# BreakOut_20172.net
KiCad netlist of a schematic drawn in Altium Designer
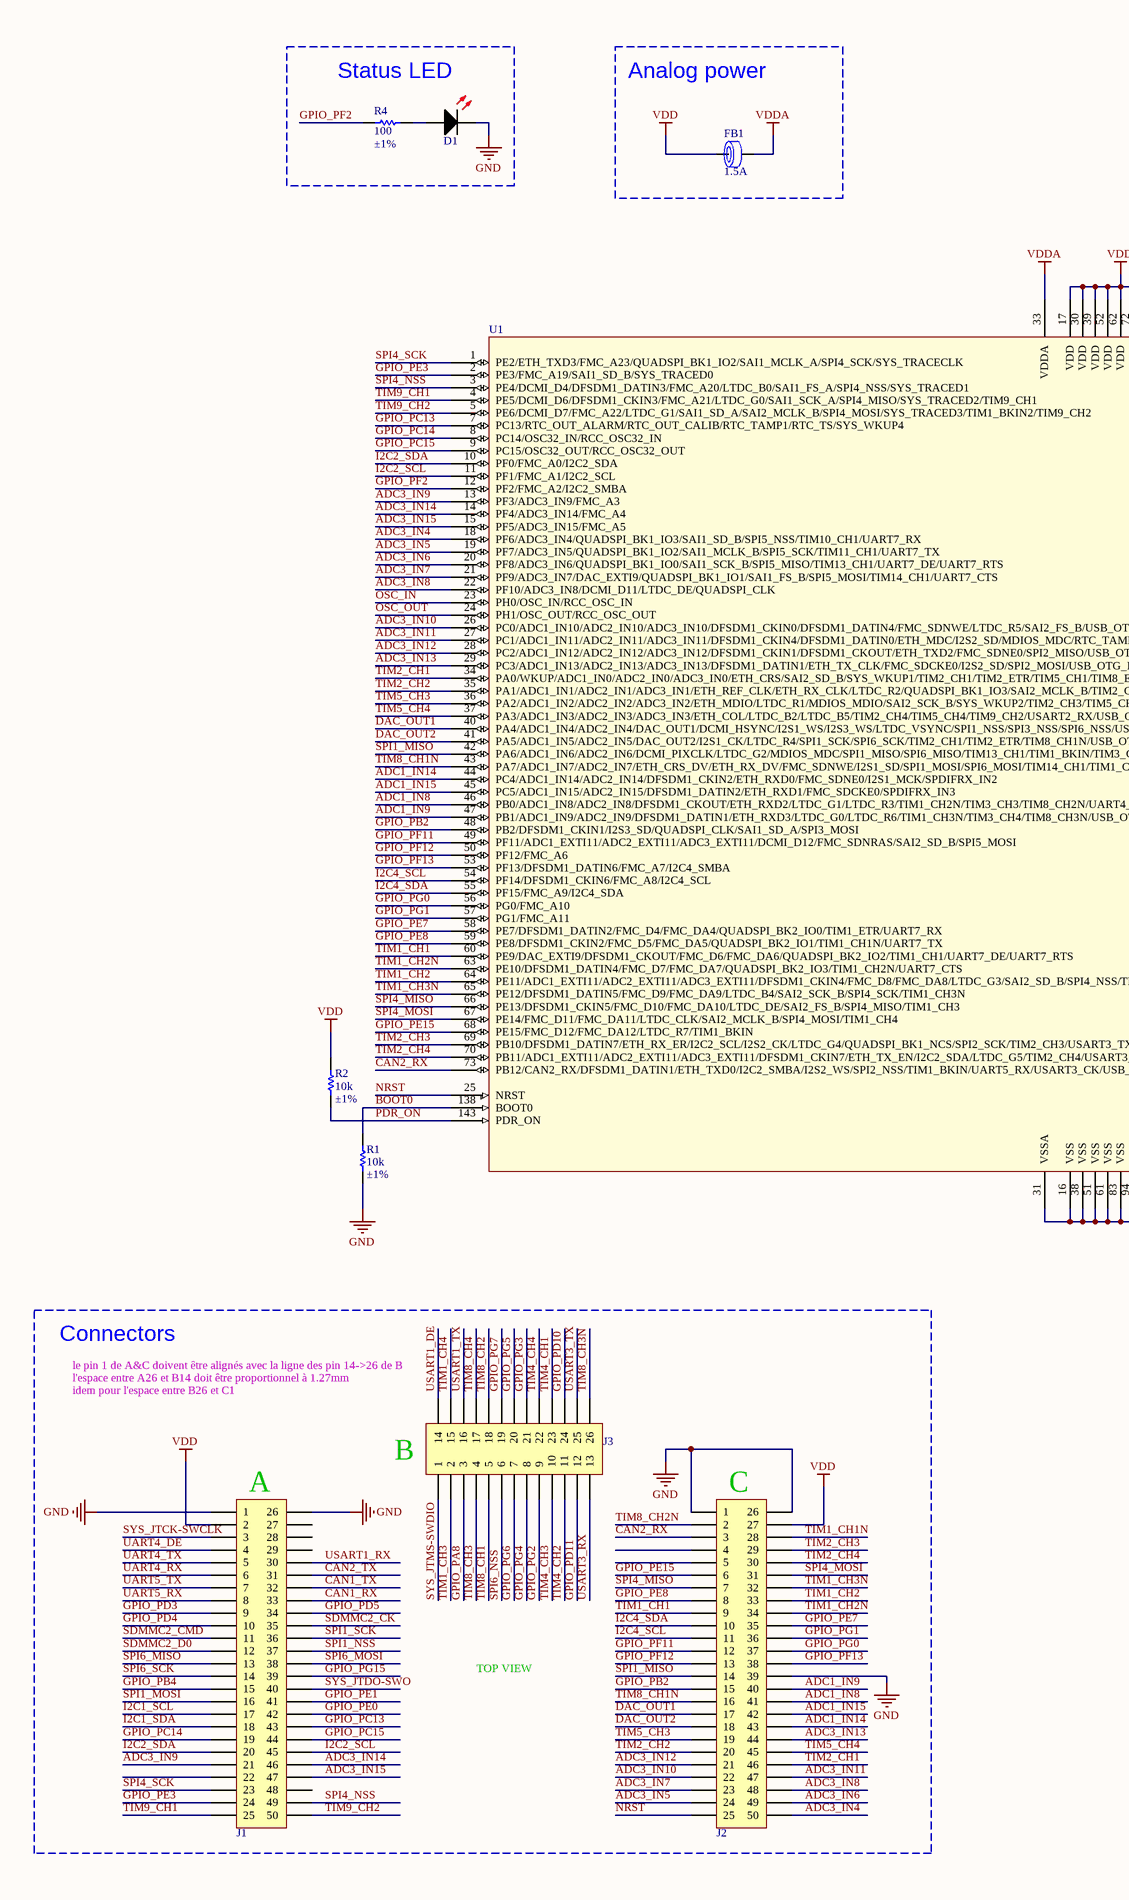
[diagram p0: BreakOut_20172.SchDoc, left]
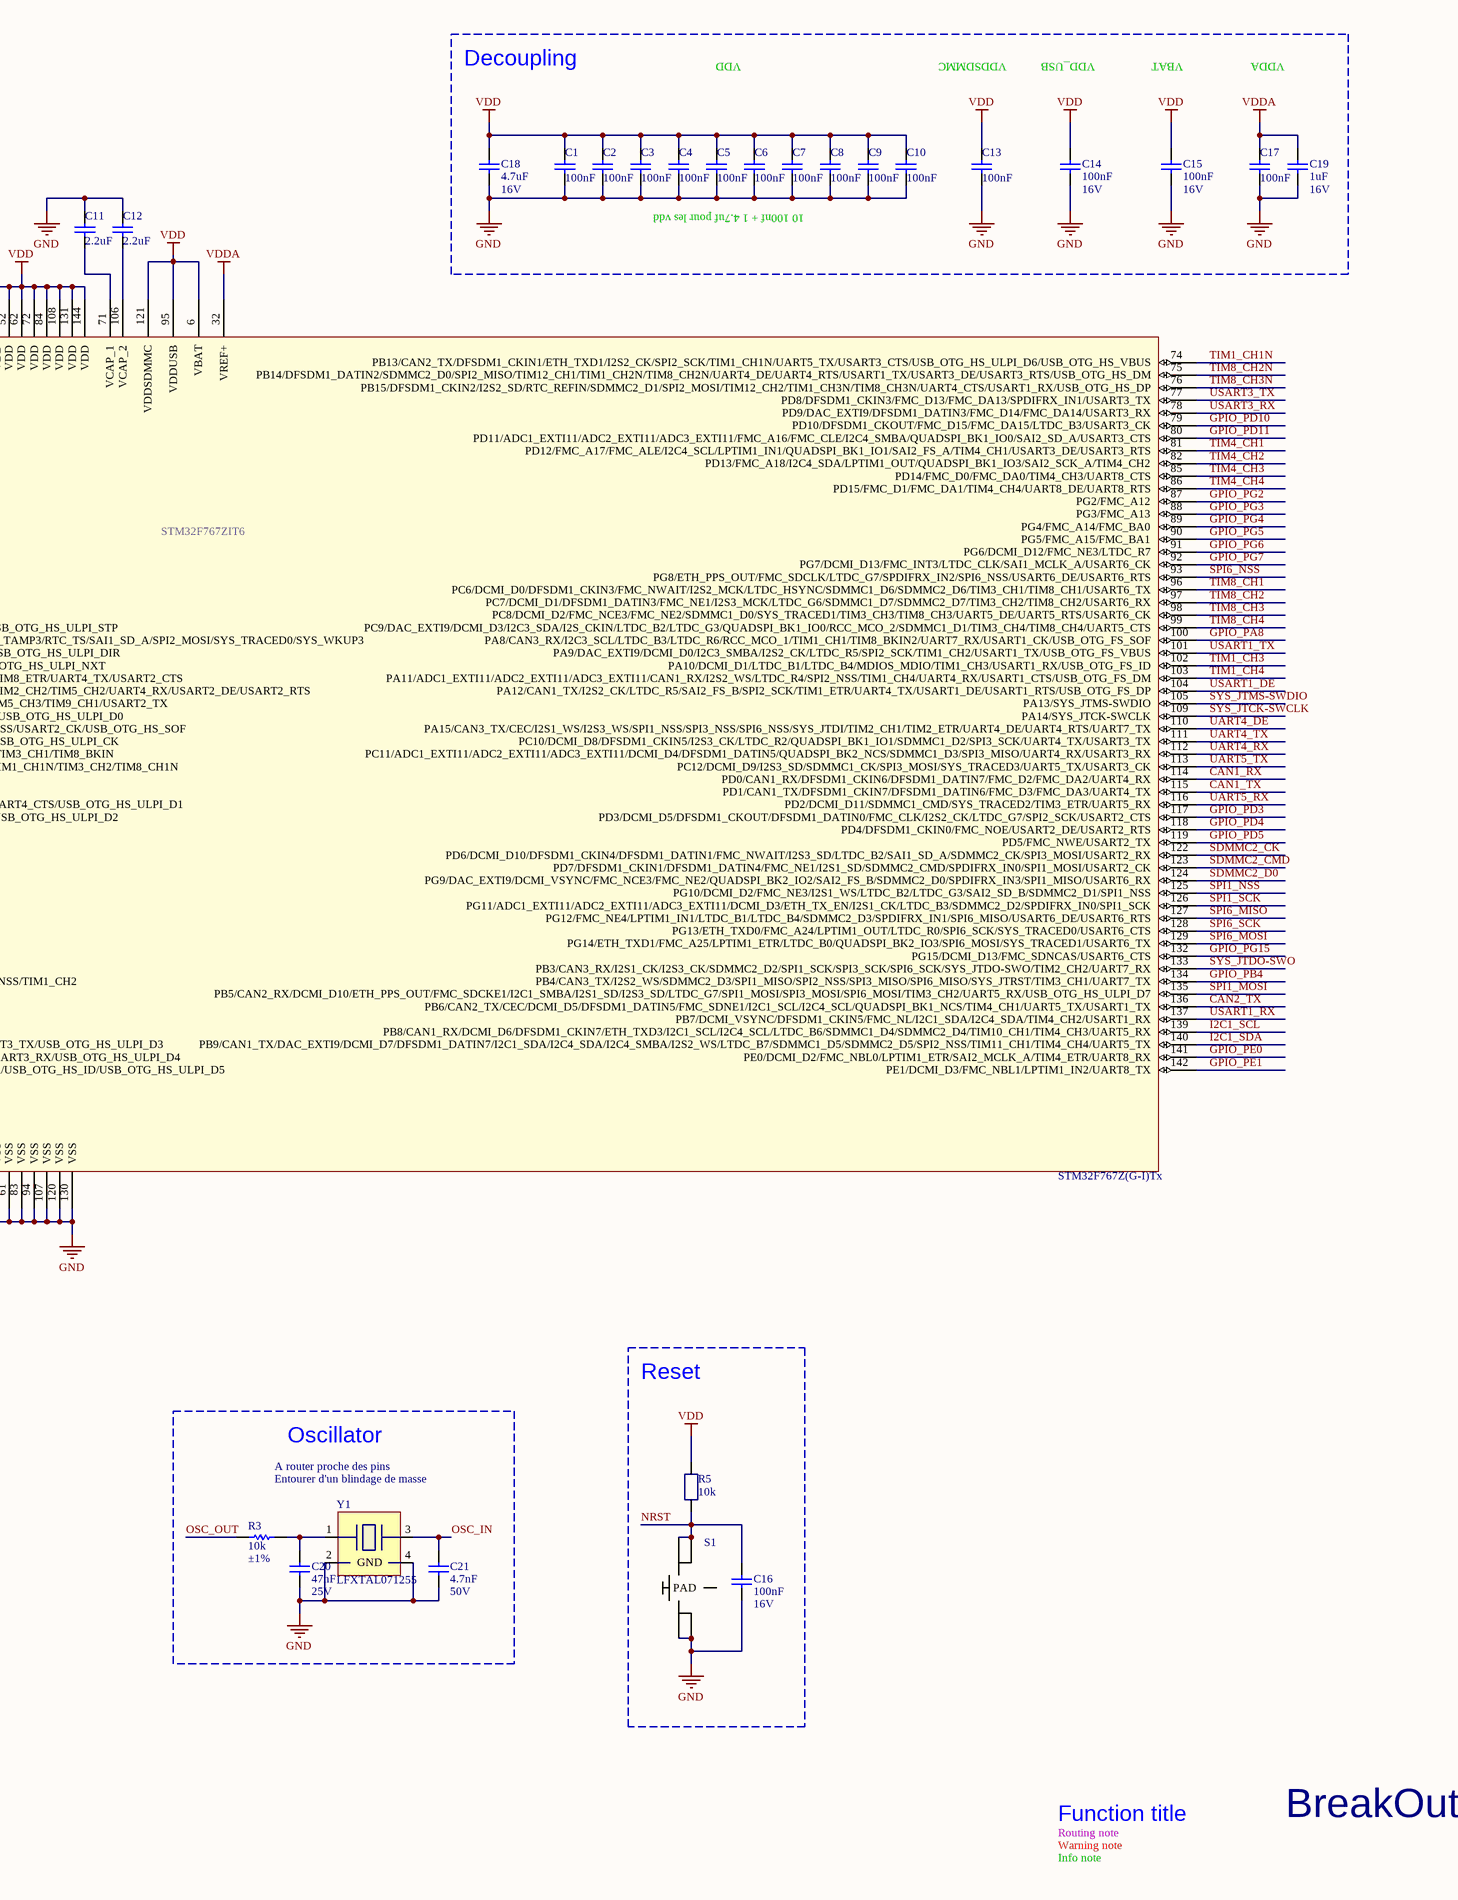
[diagram p1: BreakOut_20172.SchDoc, right]

(export (version "E")
  (design (tool "Eeschema 10.0.6"))
  (components
    (comp (ref "C1")
      (value "100nF")
      (footprint "WCAP-CSGP_0402, 1x0.5x0.5")
      (description "CAP CER 100nF 16V X7R 0402")
      (fields
        (field (name "MANUFACTURER") "Wurth Elektronik")
        (field (name "MANUFACTURER PART NUMBER") "885012205037")
      )
      (libsource (lib "Condensateur") (part "WCAP-CSGP, 885012205037"))
    )
    (comp (ref "C2")
      (value "100nF")
      (footprint "WCAP-CSGP_0402, 1x0.5x0.5")
      (description "CAP CER 100nF 16V X7R 0402")
      (fields
        (field (name "MANUFACTURER") "Wurth Elektronik")
        (field (name "MANUFACTURER PART NUMBER") "885012205037")
      )
      (libsource (lib "Condensateur") (part "WCAP-CSGP, 885012205037"))
    )
    (comp (ref "C3")
      (value "100nF")
      (footprint "WCAP-CSGP_0402, 1x0.5x0.5")
      (description "CAP CER 100nF 16V X7R 0402")
      (fields
        (field (name "MANUFACTURER") "Wurth Elektronik")
        (field (name "MANUFACTURER PART NUMBER") "885012205037")
      )
      (libsource (lib "Condensateur") (part "WCAP-CSGP, 885012205037"))
    )
    (comp (ref "C4")
      (value "100nF")
      (footprint "WCAP-CSGP_0402, 1x0.5x0.5")
      (description "CAP CER 100nF 16V X7R 0402")
      (fields
        (field (name "MANUFACTURER") "Wurth Elektronik")
        (field (name "MANUFACTURER PART NUMBER") "885012205037")
      )
      (libsource (lib "Condensateur") (part "WCAP-CSGP, 885012205037"))
    )
    (comp (ref "C5")
      (value "100nF")
      (footprint "WCAP-CSGP_0402, 1x0.5x0.5")
      (description "CAP CER 100nF 16V X7R 0402")
      (fields
        (field (name "MANUFACTURER") "Wurth Elektronik")
        (field (name "MANUFACTURER PART NUMBER") "885012205037")
      )
      (libsource (lib "Condensateur") (part "WCAP-CSGP, 885012205037"))
    )
    (comp (ref "C6")
      (value "100nF")
      (footprint "WCAP-CSGP_0402, 1x0.5x0.5")
      (description "CAP CER 100nF 16V X7R 0402")
      (fields
        (field (name "MANUFACTURER") "Wurth Elektronik")
        (field (name "MANUFACTURER PART NUMBER") "885012205037")
      )
      (libsource (lib "Condensateur") (part "WCAP-CSGP, 885012205037"))
    )
    (comp (ref "C7")
      (value "100nF")
      (footprint "WCAP-CSGP_0402, 1x0.5x0.5")
      (description "CAP CER 100nF 16V X7R 0402")
      (fields
        (field (name "MANUFACTURER") "Wurth Elektronik")
        (field (name "MANUFACTURER PART NUMBER") "885012205037")
      )
      (libsource (lib "Condensateur") (part "WCAP-CSGP, 885012205037"))
    )
    (comp (ref "C8")
      (value "100nF")
      (footprint "WCAP-CSGP_0402, 1x0.5x0.5")
      (description "CAP CER 100nF 16V X7R 0402")
      (fields
        (field (name "MANUFACTURER") "Wurth Elektronik")
        (field (name "MANUFACTURER PART NUMBER") "885012205037")
      )
      (libsource (lib "Condensateur") (part "WCAP-CSGP, 885012205037"))
    )
    (comp (ref "C9")
      (value "100nF")
      (footprint "WCAP-CSGP_0402, 1x0.5x0.5")
      (description "CAP CER 100nF 16V X7R 0402")
      (fields
        (field (name "MANUFACTURER") "Wurth Elektronik")
        (field (name "MANUFACTURER PART NUMBER") "885012205037")
      )
      (libsource (lib "Condensateur") (part "WCAP-CSGP, 885012205037"))
    )
    (comp (ref "C10")
      (value "100nF")
      (footprint "WCAP-CSGP_0402, 1x0.5x0.5")
      (description "CAP CER 100nF 16V X7R 0402")
      (fields
        (field (name "MANUFACTURER") "Wurth Elektronik")
        (field (name "MANUFACTURER PART NUMBER") "885012205037")
      )
      (libsource (lib "Condensateur") (part "WCAP-CSGP, 885012205037"))
    )
    (comp (ref "C11")
      (value "2.2uF")
      (footprint "WCAP-CSGP_0603, 1.6x0.8x0.8")
      (description "CAP CER 2.2uF 10V X7R 0603")
      (fields
        (field (name "MANUFACTURER") "Wurth Elektronik")
        (field (name "MANUFACTURER PART NUMBER") "885012206027")
      )
      (libsource (lib "Condensateur") (part "WCAP-CSGP, 885012206027"))
    )
    (comp (ref "C12")
      (value "2.2uF")
      (footprint "WCAP-CSGP_0603, 1.6x0.8x0.8")
      (description "CAP CER 2.2uF 10V X7R 0603")
      (fields
        (field (name "MANUFACTURER") "Wurth Elektronik")
        (field (name "MANUFACTURER PART NUMBER") "885012206027")
      )
      (libsource (lib "Condensateur") (part "WCAP-CSGP, 885012206027"))
    )
    (comp (ref "C13")
      (value "100nF")
      (footprint "WCAP-CSGP_0402, 1x0.5x0.5")
      (description "CAP CER 100nF 16V X7R 0402")
      (fields
        (field (name "MANUFACTURER") "Wurth Elektronik")
        (field (name "MANUFACTURER PART NUMBER") "885012205037")
      )
      (libsource (lib "Condensateur") (part "WCAP-CSGP, 885012205037"))
    )
    (comp (ref "C14")
      (value "100nF")
      (footprint "WCAP-CSGP_0402, 1x0.5x0.5")
      (description "CAP CER 100nF 16V X7R 0402")
      (fields
        (field (name "MANUFACTURER") "Wurth Elektronik")
        (field (name "MANUFACTURER PART NUMBER") "885012205037")
        (field (name "RATEDVOLTAGE") "16V")
      )
      (libsource (lib "Condensateur") (part "WCAP-CSGP, 885012205037"))
    )
    (comp (ref "C15")
      (value "100nF")
      (footprint "WCAP-CSGP_0402, 1x0.5x0.5")
      (description "CAP CER 100nF 16V X7R 0402")
      (fields
        (field (name "MANUFACTURER") "Wurth Elektronik")
        (field (name "MANUFACTURER PART NUMBER") "885012205037")
        (field (name "RATEDVOLTAGE") "16V")
      )
      (libsource (lib "Condensateur") (part "WCAP-CSGP, 885012205037"))
    )
    (comp (ref "C16")
      (value "100nF")
      (footprint "WCAP-CSGP_0402, 1x0.5x0.5")
      (description "CAP CER 100nF 16V X7R 0402")
      (fields
        (field (name "MANUFACTURER") "Wurth Elektronik")
        (field (name "MANUFACTURER PART NUMBER") "885012205037")
        (field (name "RATEDVOLTAGE") "16V")
      )
      (libsource (lib "Condensateur") (part "WCAP-CSGP, 885012205037"))
    )
    (comp (ref "C17")
      (value "100nF")
      (footprint "WCAP-CSGP_0402, 1x0.5x0.5")
      (description "CAP CER 100nF 16V X7R 0402")
      (fields
        (field (name "MANUFACTURER") "Wurth Elektronik")
        (field (name "MANUFACTURER PART NUMBER") "885012205037")
      )
      (libsource (lib "Condensateur") (part "WCAP-CSGP, 885012205037"))
    )
    (comp (ref "C18")
      (value "4.7uF")
      (footprint "WCAP-CSGP_0805, 2x1.25x1.25")
      (description "CAP CER 4.7uF 16V X7R 0805")
      (fields
        (field (name "MANUFACTURER") "Wurth Elektronik")
        (field (name "MANUFACTURER PART NUMBER") "885012207053")
        (field (name "RATEDVOLTAGE") "16V")
      )
      (libsource (lib "Condensateur") (part "WCAP-CSGP, 885012207053"))
    )
    (comp (ref "C19")
      (value "1uF")
      (footprint "WCAP-CSGP_0603, 1.6x0.8x0.8")
      (description "CAP CER 1UF 16V X5R 0603")
      (fields
        (field (name "MANUFACTURER") "Wurth Elektronik")
        (field (name "MANUFACTURER PART NUMBER") "885012106017")
        (field (name "RATEDVOLTAGE") "16V")
      )
      (libsource (lib "Condensateur") (part "WCAP-CSGP, 885012106017"))
    )
    (comp (ref "C20")
      (value "47nF")
      (footprint "WCAP-CSGP_0402, 1x0.5x0.5")
      (description "CAP CER 47nF 25V X7R 0402")
      (fields
        (field (name "MANUFACTURER") "Wurth Elektronik")
        (field (name "MANUFACTURER PART NUMBER") "885012205054")
        (field (name "RATEDVOLTAGE") "25V")
      )
      (libsource (lib "Condensateur") (part "WCAP-CSGP, 885012205054"))
    )
    (comp (ref "C21")
      (value "4.7nF")
      (footprint "WCAP-CSGP_0402, 1x0.5x0.5")
      (description "CAP CER 4.7nF 50V X7R 0402")
      (fields
        (field (name "MANUFACTURER") "Wurth Elektronik")
        (field (name "MANUFACTURER PART NUMBER") "885012205065")
        (field (name "RATEDVOLTAGE") "50V")
      )
      (libsource (lib "Condensateur") (part "WCAP-CSGP, 885012205065"))
    )
    (comp (ref "D1")
      (value "Rouge")
      (footprint "SMCW_0603")
      (description "WL-SMCW SMD LED Rouge")
      (fields (field (name "MANUFACTURER PART NUMBER") "150060RS75000"))
      (libsource (lib "Optoélectronique") (part "LED 0603 Rouge"))
    )
    (comp (ref "FB1")
      (value "742792624")
      (footprint "WE-CBF_0603_High Current")
      (description "Ferrite Bead 180ohm 0603 max1.5A")
      (fields (field (name "MANUFACTURER") "Wurth Elektronik") (field (name "RATEDCURRENT") "1.5A"))
      (libsource (lib "Inductance") (part "WE-CBF, 742792624"))
    )
    (comp (ref "J1")
      (value "WE-1.27 mm Socket Header 623350235321")
      (footprint "623350235321")
      (description "WR-PHD 1.27 mm Dual SMT Socket Header H=2.10mm")
      (fields (field (name "MANUFACTURER PART NUMBER") "623350235321"))
      (libsource (lib "Connecteurs") (part "WE-1.27 mm Socket Header 623350235321"))
    )
    (comp (ref "J2")
      (value "WE-1.27 mm Socket Header 623350235321")
      (footprint "623350235321")
      (description "WR-PHD 1.27 mm Dual SMT Socket Header H=2.10mm")
      (fields (field (name "MANUFACTURER PART NUMBER") "623350235321"))
      (libsource (lib "Connecteurs") (part "WE-1.27 mm Socket Header 623350235321"))
    )
    (comp (ref "J3")
      (value "WE-1.27 mm Socket Header 6623326235321")
      (footprint "623326235321")
      (description "WR-PHD 1.27 mm Dual SMT Socket Header H=2.10mm")
      (fields (field (name "MANUFACTURER PART NUMBER") "623326235321"))
      (libsource (lib "Connecteurs") (part "WE-1.27 mm Socket Header 623326235321"))
    )
    (comp (ref "R1")
      (value "10k")
      (footprint "RESC1005X04N")
      (description "RES SMD 10K OHM 1% 1/16W 0402")
      (fields
        (field (name "MANUFACTURER") "Yageo")
        (field (name "MANUFACTURER PART NUMBER") "RC0402FR-0710KL")
        (field (name "PRECISION") "±1%")
      )
      (libsource (lib "Resistance") (part "RC0402FR-0710KL"))
    )
    (comp (ref "R2")
      (value "10k")
      (footprint "RESC1005X04N")
      (description "RES SMD 10K OHM 1% 1/16W 0402")
      (fields
        (field (name "MANUFACTURER") "Yageo")
        (field (name "MANUFACTURER PART NUMBER") "RC0402FR-0710KL")
        (field (name "PRECISION") "±1%")
      )
      (libsource (lib "Resistance") (part "RC0402FR-0710KL"))
    )
    (comp (ref "R3")
      (value "10k")
      (footprint "RESC1005X04N")
      (description "RES SMD 10K OHM 1% 1/16W 0402")
      (fields
        (field (name "MANUFACTURER") "Yageo")
        (field (name "MANUFACTURER PART NUMBER") "RC0402FR-0710KL")
        (field (name "PRECISION") "±1%")
      )
      (libsource (lib "Resistance") (part "RC0402FR-0710KL"))
    )
    (comp (ref "R4")
      (value "100")
      (footprint "RESC1005X04N")
      (description "RES SMD 100 OHM 1% 1/16W 0402")
      (fields
        (field (name "MANUFACTURER") "Yageo")
        (field (name "MANUFACTURER PART NUMBER") "RC0402FR-07100RL")
        (field (name "PRECISION") "±1%")
      )
      (libsource (lib "Resistance") (part "RC0402FR-07100RL"))
    )
    (comp (ref "R5")
      (value "10k")
      (footprint "R_0603_std")
      (description "Resistance 10k 5% pkg 0603")
      (fields
        (field (name "MANUFACTURER") "TE CONNECTIVITY")
        (field (name "MANUFACTURER PART NUMBER") "TLRS157550ER002FTDG")
      )
      (libsource (lib "Passif_2017") (part "R_10k_0603"))
    )
    (comp (ref "S1")
      (value "MCITPG")
      (footprint "MCIPTG23K-V")
      (description "Switch MCIPTG23K-V Multicomp")
      (fields
        (field (name "MANUFACTURER") "MULTICOMP")
        (field (name "MANUFACTURER PART NUMBER") "MCIPTG23K-V")
      )
      (libsource (lib "Switchs") (part "MCIPTG23K-V"))
    )
    (comp (ref "U1")
      (value "STM32F767Z(G-I)Tx")
      (footprint "TSQFP50P2200X2200X160-144N")
      (description "STM32F767ZIT6")
      (fields
        (field (name "MANUFACTURER") "STMICROELECTRONICS")
        (field (name "MANUFACTURER PART NUMBER") "STM32F767ZIT6")
      )
      (libsource (lib "Stm32") (part "STM32F767ZIT6"))
    )
    (comp (ref "Y1")
      (value "LFXTAL071255")
      (footprint "LFXTAL071255")
      (description "Quartz 16MHz 10pF CMS 4P ~2x1.6mm")
      (fields (field (name "MANUFACTURER") "IQD"))
      (libsource (lib "Crystal") (part "LFXTAL071255"))
    )
  )
  (nets
    (net (code "1") (name "/ADC1_IN8") (class "Default")
      (node (ref "J2") (pin "41") (pinfunction "41_41") (pintype "passive"))
      (node (ref "U1") (pin "46") (pinfunction "PB0/ADC1_IN8/ADC2_IN8/DFSDM1_CKOUT/ETH_RXD2/LTDC_G1/LTDC_R3/TIM1_CH2N/TIM3_CH3/TIM8_CH2N/UART4_CTS/USB_OTG_HS_ULPI_D1_46") (pintype "bidirectional"))
    )
    (net (code "2") (name "/ADC1_IN9") (class "Default")
      (node (ref "J2") (pin "40") (pinfunction "40_40") (pintype "passive"))
      (node (ref "U1") (pin "47") (pinfunction "PB1/ADC1_IN9/ADC2_IN9/DFSDM1_DATIN1/ETH_RXD3/LTDC_G0/LTDC_R6/TIM1_CH3N/TIM3_CH4/TIM8_CH3N/USB_OTG_HS_ULPI_D2_47") (pintype "bidirectional"))
    )
    (net (code "3") (name "/ADC1_IN14") (class "Default")
      (node (ref "J2") (pin "43") (pinfunction "43_43") (pintype "passive"))
      (node (ref "U1") (pin "44") (pinfunction "PC4/ADC1_IN14/ADC2_IN14/DFSDM1_CKIN2/ETH_RXD0/FMC_SDNE0/I2S1_MCK/SPDIFRX_IN2_44") (pintype "bidirectional"))
    )
    (net (code "4") (name "/ADC1_IN15") (class "Default")
      (node (ref "J2") (pin "42") (pinfunction "42_42") (pintype "passive"))
      (node (ref "U1") (pin "45") (pinfunction "PC5/ADC1_IN15/ADC2_IN15/DFSDM1_DATIN2/ETH_RXD1/FMC_SDCKE0/SPDIFRX_IN3_45") (pintype "bidirectional"))
    )
    (net (code "5") (name "/ADC3_IN4") (class "Default")
      (node (ref "J2") (pin "50") (pinfunction "50_50") (pintype "passive"))
      (node (ref "U1") (pin "18") (pinfunction "PF6/ADC3_IN4/QUADSPI_BK1_IO3/SAI1_SD_B/SPI5_NSS/TIM10_CH1/UART7_RX_18") (pintype "bidirectional"))
    )
    (net (code "6") (name "/ADC3_IN5") (class "Default")
      (node (ref "J2") (pin "24") (pinfunction "24_24") (pintype "passive"))
      (node (ref "U1") (pin "19") (pinfunction "PF7/ADC3_IN5/QUADSPI_BK1_IO2/SAI1_MCLK_B/SPI5_SCK/TIM11_CH1/UART7_TX_19") (pintype "bidirectional"))
    )
    (net (code "7") (name "/ADC3_IN6") (class "Default")
      (node (ref "J2") (pin "49") (pinfunction "49_49") (pintype "passive"))
      (node (ref "U1") (pin "20") (pinfunction "PF8/ADC3_IN6/QUADSPI_BK1_IO0/SAI1_SCK_B/SPI5_MISO/TIM13_CH1/UART7_DE/UART7_RTS_20") (pintype "bidirectional"))
    )
    (net (code "8") (name "/ADC3_IN7") (class "Default")
      (node (ref "J2") (pin "23") (pinfunction "23_23") (pintype "passive"))
      (node (ref "U1") (pin "21") (pinfunction "PF9/ADC3_IN7/DAC_EXTI9/QUADSPI_BK1_IO1/SAI1_FS_B/SPI5_MOSI/TIM14_CH1/UART7_CTS_21") (pintype "bidirectional"))
    )
    (net (code "9") (name "/ADC3_IN8") (class "Default")
      (node (ref "J2") (pin "48") (pinfunction "48_48") (pintype "passive"))
      (node (ref "U1") (pin "22") (pinfunction "PF10/ADC3_IN8/DCMI_D11/LTDC_DE/QUADSPI_CLK_22") (pintype "bidirectional"))
    )
    (net (code "10") (name "/ADC3_IN9") (class "Default")
      (node (ref "J1") (pin "21") (pinfunction "21_21") (pintype "passive"))
      (node (ref "U1") (pin "13") (pinfunction "PF3/ADC3_IN9/FMC_A3_13") (pintype "bidirectional"))
    )
    (net (code "11") (name "/ADC3_IN10") (class "Default")
      (node (ref "J2") (pin "22") (pinfunction "22_22") (pintype "passive"))
      (node (ref "U1") (pin "26") (pinfunction "PC0/ADC1_IN10/ADC2_IN10/ADC3_IN10/DFSDM1_CKIN0/DFSDM1_DATIN4/FMC_SDNWE/LTDC_R5/SAI2_FS_B/USB_OTG_HS_ULPI_STP_26") (pintype "bidirectional"))
    )
    (net (code "12") (name "/ADC3_IN11") (class "Default")
      (node (ref "J2") (pin "47") (pinfunction "47_47") (pintype "passive"))
      (node (ref "U1") (pin "27") (pinfunction "PC1/ADC1_IN11/ADC2_IN11/ADC3_IN11/DFSDM1_CKIN4/DFSDM1_DATIN0/ETH_MDC/I2S2_SD/MDIOS_MDC/RTC_TAMP3/RTC_TS/SAI1_SD_A/SPI2_MOSI/SYS_TRACED0/SYS_WKUP3_27") (pintype "bidirectional"))
    )
    (net (code "13") (name "/ADC3_IN12") (class "Default")
      (node (ref "J2") (pin "21") (pinfunction "21_21") (pintype "passive"))
      (node (ref "U1") (pin "28") (pinfunction "PC2/ADC1_IN12/ADC2_IN12/ADC3_IN12/DFSDM1_CKIN1/DFSDM1_CKOUT/ETH_TXD2/FMC_SDNE0/SPI2_MISO/USB_OTG_HS_ULPI_DIR_28") (pintype "bidirectional"))
    )
    (net (code "14") (name "/ADC3_IN13") (class "Default")
      (node (ref "J2") (pin "44") (pinfunction "44_44") (pintype "passive"))
      (node (ref "U1") (pin "29") (pinfunction "PC3/ADC1_IN13/ADC2_IN13/ADC3_IN13/DFSDM1_DATIN1/ETH_TX_CLK/FMC_SDCKE0/I2S2_SD/SPI2_MOSI/USB_OTG_HS_ULPI_NXT_29") (pintype "bidirectional"))
    )
    (net (code "15") (name "/ADC3_IN14") (class "Default")
      (node (ref "J1") (pin "46") (pinfunction "46_46") (pintype "passive"))
      (node (ref "U1") (pin "14") (pinfunction "PF4/ADC3_IN14/FMC_A4_14") (pintype "bidirectional"))
    )
    (net (code "16") (name "/ADC3_IN15") (class "Default")
      (node (ref "J1") (pin "47") (pinfunction "47_47") (pintype "passive"))
      (node (ref "U1") (pin "15") (pinfunction "PF5/ADC3_IN15/FMC_A5_15") (pintype "bidirectional"))
    )
    (net (code "17") (name "/BOOT0") (class "Default")
      (node (ref "R1") (pin "2") (pinfunction "2_2") (pintype "passive"))
      (node (ref "U1") (pin "138") (pinfunction "BOOT0_138") (pintype "input"))
    )
    (net (code "18") (name "/CAN1_RX") (class "Default")
      (node (ref "J1") (pin "33") (pinfunction "33_33") (pintype "passive"))
      (node (ref "U1") (pin "114") (pinfunction "PD0/CAN1_RX/DFSDM1_CKIN6/DFSDM1_DATIN7/FMC_D2/FMC_DA2/UART4_RX_114") (pintype "bidirectional"))
    )
    (net (code "19") (name "/CAN1_TX") (class "Default")
      (node (ref "J1") (pin "32") (pinfunction "32_32") (pintype "passive"))
      (node (ref "U1") (pin "115") (pinfunction "PD1/CAN1_TX/DFSDM1_CKIN7/DFSDM1_DATIN6/FMC_D3/FMC_DA3/UART4_TX_115") (pintype "bidirectional"))
    )
    (net (code "20") (name "/CAN2_RX") (class "Default")
      (node (ref "J2") (pin "3") (pinfunction "3_3") (pintype "passive"))
      (node (ref "U1") (pin "73") (pinfunction "PB12/CAN2_RX/DFSDM1_DATIN1/ETH_TXD0/I2C2_SMBA/I2S2_WS/SPI2_NSS/TIM1_BKIN/UART5_RX/USART3_CK/USB_OTG_HS_ID/USB_OTG_HS_ULPI_D5_73") (pintype "bidirectional"))
    )
    (net (code "21") (name "/CAN2_TX") (class "Default")
      (node (ref "J1") (pin "31") (pinfunction "31_31") (pintype "passive"))
      (node (ref "U1") (pin "136") (pinfunction "PB6/CAN2_TX/CEC/DCMI_D5/DFSDM1_DATIN5/FMC_SDNE1/I2C1_SCL/I2C4_SCL/QUADSPI_BK1_NCS/TIM4_CH1/UART5_TX/USART1_TX_136") (pintype "bidirectional"))
    )
    (net (code "22") (name "/DAC_OUT1") (class "Default")
      (node (ref "J2") (pin "17") (pinfunction "17_17") (pintype "passive"))
      (node (ref "U1") (pin "40") (pinfunction "PA4/ADC1_IN4/ADC2_IN4/DAC_OUT1/DCMI_HSYNC/I2S1_WS/I2S3_WS/LTDC_VSYNC/SPI1_NSS/SPI3_NSS/SPI6_NSS/USART2_CK/USB_OTG_HS_SOF_40") (pintype "bidirectional"))
    )
    (net (code "23") (name "/DAC_OUT2") (class "Default")
      (node (ref "J2") (pin "18") (pinfunction "18_18") (pintype "passive"))
      (node (ref "U1") (pin "41") (pinfunction "PA5/ADC1_IN5/ADC2_IN5/DAC_OUT2/I2S1_CK/LTDC_R4/SPI1_SCK/SPI6_SCK/TIM2_CH1/TIM2_ETR/TIM8_CH1N/USB_OTG_HS_ULPI_CK_41") (pintype "bidirectional"))
    )
    (net (code "24") (name "/GPIO_PA8") (class "Default")
      (node (ref "J3") (pin "3") (pinfunction "3_3") (pintype "passive"))
      (node (ref "U1") (pin "100") (pinfunction "PA8/CAN3_RX/I2C3_SCL/LTDC_B3/LTDC_R6/RCC_MCO_1/TIM1_CH1/TIM8_BKIN2/UART7_RX/USART1_CK/USB_OTG_FS_SOF_100") (pintype "bidirectional"))
    )
    (net (code "25") (name "/GPIO_PB2") (class "Default")
      (node (ref "J2") (pin "15") (pinfunction "15_15") (pintype "passive"))
      (node (ref "U1") (pin "48") (pinfunction "PB2/DFSDM1_CKIN1/I2S3_SD/QUADSPI_CLK/SAI1_SD_A/SPI3_MOSI_48") (pintype "bidirectional"))
    )
    (net (code "26") (name "/GPIO_PB4") (class "Default")
      (node (ref "J1") (pin "15") (pinfunction "15_15") (pintype "passive"))
      (node (ref "U1") (pin "134") (pinfunction "PB4/CAN3_TX/I2S2_WS/SDMMC2_D3/SPI1_MISO/SPI2_NSS/SPI3_MISO/SPI6_MISO/SYS_JTRST/TIM3_CH1/UART7_TX_134") (pintype "bidirectional"))
    )
    (net (code "27") (name "/GPIO_PC13") (class "Default")
      (node (ref "J1") (pin "43") (pinfunction "43_43") (pintype "passive"))
      (node (ref "U1") (pin "7") (pinfunction "PC13/RTC_OUT_ALARM/RTC_OUT_CALIB/RTC_TAMP1/RTC_TS/SYS_WKUP4_7") (pintype "bidirectional"))
    )
    (net (code "28") (name "/GPIO_PC14") (class "Default")
      (node (ref "J1") (pin "19") (pinfunction "19_19") (pintype "passive"))
      (node (ref "U1") (pin "8") (pinfunction "PC14/OSC32_IN/RCC_OSC32_IN_8") (pintype "bidirectional"))
    )
    (net (code "29") (name "/GPIO_PC15") (class "Default")
      (node (ref "J1") (pin "44") (pinfunction "44_44") (pintype "passive"))
      (node (ref "U1") (pin "9") (pinfunction "PC15/OSC32_OUT/RCC_OSC32_OUT_9") (pintype "bidirectional"))
    )
    (net (code "30") (name "/GPIO_PD3") (class "Default")
      (node (ref "J1") (pin "9") (pinfunction "9_9") (pintype "passive"))
      (node (ref "U1") (pin "117") (pinfunction "PD3/DCMI_D5/DFSDM1_CKOUT/DFSDM1_DATIN0/FMC_CLK/I2S2_CK/LTDC_G7/SPI2_SCK/USART2_CTS_117") (pintype "bidirectional"))
    )
    (net (code "31") (name "/GPIO_PD4") (class "Default")
      (node (ref "J1") (pin "10") (pinfunction "10_10") (pintype "passive"))
      (node (ref "U1") (pin "118") (pinfunction "PD4/DFSDM1_CKIN0/FMC_NOE/USART2_DE/USART2_RTS_118") (pintype "bidirectional"))
    )
    (net (code "32") (name "/GPIO_PD5") (class "Default")
      (node (ref "J1") (pin "34") (pinfunction "34_34") (pintype "passive"))
      (node (ref "U1") (pin "119") (pinfunction "PD5/FMC_NWE/USART2_TX_119") (pintype "bidirectional"))
    )
    (net (code "33") (name "/GPIO_PD10") (class "Default")
      (node (ref "J3") (pin "24") (pinfunction "24_24") (pintype "passive"))
      (node (ref "U1") (pin "79") (pinfunction "PD10/DFSDM1_CKOUT/FMC_D15/FMC_DA15/LTDC_B3/USART3_CK_79") (pintype "bidirectional"))
    )
    (net (code "34") (name "/GPIO_PD11") (class "Default")
      (node (ref "J3") (pin "12") (pinfunction "12_12") (pintype "passive"))
      (node (ref "U1") (pin "80") (pinfunction "PD11/ADC1_EXTI11/ADC2_EXTI11/ADC3_EXTI11/FMC_A16/FMC_CLE/I2C4_SMBA/QUADSPI_BK1_IO0/SAI2_SD_A/USART3_CTS_80") (pintype "bidirectional"))
    )
    (net (code "35") (name "/GPIO_PE0") (class "Default")
      (node (ref "J1") (pin "42") (pinfunction "42_42") (pintype "passive"))
      (node (ref "U1") (pin "141") (pinfunction "PE0/DCMI_D2/FMC_NBL0/LPTIM1_ETR/SAI2_MCLK_A/TIM4_ETR/UART8_RX_141") (pintype "bidirectional"))
    )
    (net (code "36") (name "/GPIO_PE1") (class "Default")
      (node (ref "J1") (pin "41") (pinfunction "41_41") (pintype "passive"))
      (node (ref "U1") (pin "142") (pinfunction "PE1/DCMI_D3/FMC_NBL1/LPTIM1_IN2/UART8_TX_142") (pintype "bidirectional"))
    )
    (net (code "37") (name "/GPIO_PE3") (class "Default")
      (node (ref "J1") (pin "24") (pinfunction "24_24") (pintype "passive"))
      (node (ref "U1") (pin "2") (pinfunction "PE3/FMC_A19/SAI1_SD_B/SYS_TRACED0_2") (pintype "bidirectional"))
    )
    (net (code "38") (name "/GPIO_PE7") (class "Default")
      (node (ref "J2") (pin "35") (pinfunction "35_35") (pintype "passive"))
      (node (ref "U1") (pin "58") (pinfunction "PE7/DFSDM1_DATIN2/FMC_D4/FMC_DA4/QUADSPI_BK2_IO0/TIM1_ETR/UART7_RX_58") (pintype "bidirectional"))
    )
    (net (code "39") (name "/GPIO_PE8") (class "Default")
      (node (ref "J2") (pin "8") (pinfunction "8_8") (pintype "passive"))
      (node (ref "U1") (pin "59") (pinfunction "PE8/DFSDM1_CKIN2/FMC_D5/FMC_DA5/QUADSPI_BK2_IO1/TIM1_CH1N/UART7_TX_59") (pintype "bidirectional"))
    )
    (net (code "40") (name "/GPIO_PE15") (class "Default")
      (node (ref "J2") (pin "6") (pinfunction "6_6") (pintype "passive"))
      (node (ref "U1") (pin "68") (pinfunction "PE15/FMC_D12/FMC_DA12/LTDC_R7/TIM1_BKIN_68") (pintype "bidirectional"))
    )
    (net (code "41") (name "/GPIO_PF2") (class "Default")
      (node (ref "R4") (pin "2") (pinfunction "2_2") (pintype "passive"))
      (node (ref "U1") (pin "12") (pinfunction "PF2/FMC_A2/I2C2_SMBA_12") (pintype "bidirectional"))
    )
    (net (code "42") (name "/GPIO_PF11") (class "Default")
      (node (ref "J2") (pin "12") (pinfunction "12_12") (pintype "passive"))
      (node (ref "U1") (pin "49") (pinfunction "PF11/ADC1_EXTI11/ADC2_EXTI11/ADC3_EXTI11/DCMI_D12/FMC_SDNRAS/SAI2_SD_B/SPI5_MOSI_49") (pintype "bidirectional"))
    )
    (net (code "43") (name "/GPIO_PF12") (class "Default")
      (node (ref "J2") (pin "13") (pinfunction "13_13") (pintype "passive"))
      (node (ref "U1") (pin "50") (pinfunction "PF12/FMC_A6_50") (pintype "bidirectional"))
    )
    (net (code "44") (name "/GPIO_PF13") (class "Default")
      (node (ref "J2") (pin "38") (pinfunction "38_38") (pintype "passive"))
      (node (ref "U1") (pin "53") (pinfunction "PF13/DFSDM1_DATIN6/FMC_A7/I2C4_SMBA_53") (pintype "bidirectional"))
    )
    (net (code "45") (name "/GPIO_PG0") (class "Default")
      (node (ref "J2") (pin "37") (pinfunction "37_37") (pintype "passive"))
      (node (ref "U1") (pin "56") (pinfunction "PG0/FMC_A10_56") (pintype "bidirectional"))
    )
    (net (code "46") (name "/GPIO_PG1") (class "Default")
      (node (ref "J2") (pin "36") (pinfunction "36_36") (pintype "passive"))
      (node (ref "U1") (pin "57") (pinfunction "PG1/FMC_A11_57") (pintype "bidirectional"))
    )
    (net (code "47") (name "/GPIO_PG2") (class "Default")
      (node (ref "J3") (pin "9") (pinfunction "9_9") (pintype "passive"))
      (node (ref "U1") (pin "87") (pinfunction "PG2/FMC_A12_87") (pintype "bidirectional"))
    )
    (net (code "48") (name "/GPIO_PG3") (class "Default")
      (node (ref "J3") (pin "21") (pinfunction "21_21") (pintype "passive"))
      (node (ref "U1") (pin "88") (pinfunction "PG3/FMC_A13_88") (pintype "bidirectional"))
    )
    (net (code "49") (name "/GPIO_PG4") (class "Default")
      (node (ref "J3") (pin "8") (pinfunction "8_8") (pintype "passive"))
      (node (ref "U1") (pin "89") (pinfunction "PG4/FMC_A14/FMC_BA0_89") (pintype "bidirectional"))
    )
    (net (code "50") (name "/GPIO_PG5") (class "Default")
      (node (ref "J3") (pin "20") (pinfunction "20_20") (pintype "passive"))
      (node (ref "U1") (pin "90") (pinfunction "PG5/FMC_A15/FMC_BA1_90") (pintype "bidirectional"))
    )
    (net (code "51") (name "/GPIO_PG6") (class "Default")
      (node (ref "J3") (pin "7") (pinfunction "7_7") (pintype "passive"))
      (node (ref "U1") (pin "91") (pinfunction "PG6/DCMI_D12/FMC_NE3/LTDC_R7_91") (pintype "bidirectional"))
    )
    (net (code "52") (name "/GPIO_PG7") (class "Default")
      (node (ref "J3") (pin "19") (pinfunction "19_19") (pintype "passive"))
      (node (ref "U1") (pin "92") (pinfunction "PG7/DCMI_D13/FMC_INT3/LTDC_CLK/SAI1_MCLK_A/USART6_CK_92") (pintype "bidirectional"))
    )
    (net (code "53") (name "/GPIO_PG15") (class "Default")
      (node (ref "J1") (pin "39") (pinfunction "39_39") (pintype "passive"))
      (node (ref "U1") (pin "132") (pinfunction "PG15/DCMI_D13/FMC_SDNCAS/USART6_CTS_132") (pintype "bidirectional"))
    )
    (net (code "54") (name "/I2C1_SCL") (class "Default")
      (node (ref "J1") (pin "17") (pinfunction "17_17") (pintype "passive"))
      (node (ref "U1") (pin "139") (pinfunction "PB8/CAN1_RX/DCMI_D6/DFSDM1_CKIN7/ETH_TXD3/I2C1_SCL/I2C4_SCL/LTDC_B6/SDMMC1_D4/SDMMC2_D4/TIM10_CH1/TIM4_CH3/UART5_RX_139") (pintype "bidirectional"))
    )
    (net (code "55") (name "/I2C1_SDA") (class "Default")
      (node (ref "J1") (pin "18") (pinfunction "18_18") (pintype "passive"))
      (node (ref "U1") (pin "140") (pinfunction "PB9/CAN1_TX/DAC_EXTI9/DCMI_D7/DFSDM1_DATIN7/I2C1_SDA/I2C4_SDA/I2C4_SMBA/I2S2_WS/LTDC_B7/SDMMC1_D5/SDMMC2_D5/SPI2_NSS/TIM11_CH1/TIM4_CH4/UART5_TX_140") (pintype "bidirectional"))
    )
    (net (code "56") (name "/I2C2_SCL") (class "Default")
      (node (ref "J1") (pin "45") (pinfunction "45_45") (pintype "passive"))
      (node (ref "U1") (pin "11") (pinfunction "PF1/FMC_A1/I2C2_SCL_11") (pintype "bidirectional"))
    )
    (net (code "57") (name "/I2C2_SDA") (class "Default")
      (node (ref "J1") (pin "20") (pinfunction "20_20") (pintype "passive"))
      (node (ref "U1") (pin "10") (pinfunction "PF0/FMC_A0/I2C2_SDA_10") (pintype "bidirectional"))
    )
    (net (code "58") (name "/I2C4_SCL") (class "Default")
      (node (ref "J2") (pin "11") (pinfunction "11_11") (pintype "passive"))
      (node (ref "U1") (pin "54") (pinfunction "PF14/DFSDM1_CKIN6/FMC_A8/I2C4_SCL_54") (pintype "bidirectional"))
    )
    (net (code "59") (name "/I2C4_SDA") (class "Default")
      (node (ref "J2") (pin "10") (pinfunction "10_10") (pintype "passive"))
      (node (ref "U1") (pin "55") (pinfunction "PF15/FMC_A9/I2C4_SDA_55") (pintype "bidirectional"))
    )
    (net (code "60") (name "/NRST") (class "Default")
      (node (ref "C16") (pin "2") (pinfunction "2_2") (pintype "passive"))
      (node (ref "J2") (pin "25") (pinfunction "25_25") (pintype "passive"))
      (node (ref "R5") (pin "2") (pinfunction "2_2") (pintype "passive"))
      (node (ref "S1") (pin "2") (pinfunction "2_2") (pintype "passive"))
      (node (ref "S1") (pin "4") (pinfunction "4_4") (pintype "passive"))
      (node (ref "U1") (pin "25") (pinfunction "NRST_25") (pintype "input"))
    )
    (net (code "61") (name "/OSC_IN") (class "Default")
      (node (ref "C21") (pin "2") (pinfunction "2_2") (pintype "passive"))
      (node (ref "U1") (pin "23") (pinfunction "PH0/OSC_IN/RCC_OSC_IN_23") (pintype "bidirectional"))
      (node (ref "Y1") (pin "3") (pinfunction "3_3") (pintype "passive"))
    )
    (net (code "62") (name "/OSC_OUT") (class "Default")
      (node (ref "R3") (pin "2") (pinfunction "2_2") (pintype "passive"))
      (node (ref "U1") (pin "24") (pinfunction "PH1/OSC_OUT/RCC_OSC_OUT_24") (pintype "bidirectional"))
    )
    (net (code "63") (name "/PDR_ON") (class "Default")
      (node (ref "R2") (pin "1") (pinfunction "1_1") (pintype "passive"))
      (node (ref "U1") (pin "143") (pinfunction "PDR_ON_143") (pintype "input"))
    )
    (net (code "64") (name "/SDMMC2_CK") (class "Default")
      (node (ref "J1") (pin "35") (pinfunction "35_35") (pintype "passive"))
      (node (ref "U1") (pin "122") (pinfunction "PD6/DCMI_D10/DFSDM1_CKIN4/DFSDM1_DATIN1/FMC_NWAIT/I2S3_SD/LTDC_B2/SAI1_SD_A/SDMMC2_CK/SPI3_MOSI/USART2_RX_122") (pintype "bidirectional"))
    )
    (net (code "65") (name "/SDMMC2_CMD") (class "Default")
      (node (ref "J1") (pin "11") (pinfunction "11_11") (pintype "passive"))
      (node (ref "U1") (pin "123") (pinfunction "PD7/DFSDM1_CKIN1/DFSDM1_DATIN4/FMC_NE1/I2S1_SD/SDMMC2_CMD/SPDIFRX_IN0/SPI1_MOSI/USART2_CK_123") (pintype "bidirectional"))
    )
    (net (code "66") (name "/SDMMC2_D0") (class "Default")
      (node (ref "J1") (pin "12") (pinfunction "12_12") (pintype "passive"))
      (node (ref "U1") (pin "124") (pinfunction "PG9/DAC_EXTI9/DCMI_VSYNC/FMC_NCE3/FMC_NE2/QUADSPI_BK2_IO2/SAI2_FS_B/SDMMC2_D0/SPDIFRX_IN3/SPI1_MISO/USART6_RX_124") (pintype "bidirectional"))
    )
    (net (code "67") (name "/SPI1_MISO") (class "Default")
      (node (ref "J2") (pin "14") (pinfunction "14_14") (pintype "passive"))
      (node (ref "U1") (pin "42") (pinfunction "PA6/ADC1_IN6/ADC2_IN6/DCMI_PIXCLK/LTDC_G2/MDIOS_MDC/SPI1_MISO/SPI6_MISO/TIM13_CH1/TIM1_BKIN/TIM3_CH1/TIM8_BKIN_42") (pintype "bidirectional"))
    )
    (net (code "68") (name "/SPI1_MOSI") (class "Default")
      (node (ref "J1") (pin "16") (pinfunction "16_16") (pintype "passive"))
      (node (ref "U1") (pin "135") (pinfunction "PB5/CAN2_RX/DCMI_D10/ETH_PPS_OUT/FMC_SDCKE1/I2C1_SMBA/I2S1_SD/I2S3_SD/LTDC_G7/SPI1_MOSI/SPI3_MOSI/SPI6_MOSI/TIM3_CH2/UART5_RX/USB_OTG_HS_ULPI_D7_135") (pintype "bidirectional"))
    )
    (net (code "69") (name "/SPI1_NSS") (class "Default")
      (node (ref "J1") (pin "37") (pinfunction "37_37") (pintype "passive"))
      (node (ref "U1") (pin "125") (pinfunction "PG10/DCMI_D2/FMC_NE3/I2S1_WS/LTDC_B2/LTDC_G3/SAI2_SD_B/SDMMC2_D1/SPI1_NSS_125") (pintype "bidirectional"))
    )
    (net (code "70") (name "/SPI1_SCK") (class "Default")
      (node (ref "J1") (pin "36") (pinfunction "36_36") (pintype "passive"))
      (node (ref "U1") (pin "126") (pinfunction "PG11/ADC1_EXTI11/ADC2_EXTI11/ADC3_EXTI11/DCMI_D3/ETH_TX_EN/I2S1_CK/LTDC_B3/SDMMC2_D2/SPDIFRX_IN0/SPI1_SCK_126") (pintype "bidirectional"))
    )
    (net (code "71") (name "/SPI4_MISO") (class "Default")
      (node (ref "J2") (pin "7") (pinfunction "7_7") (pintype "passive"))
      (node (ref "U1") (pin "66") (pinfunction "PE13/DFSDM1_CKIN5/FMC_D10/FMC_DA10/LTDC_DE/SAI2_FS_B/SPI4_MISO/TIM1_CH3_66") (pintype "bidirectional"))
    )
    (net (code "72") (name "/SPI4_MOSI") (class "Default")
      (node (ref "J2") (pin "31") (pinfunction "31_31") (pintype "passive"))
      (node (ref "U1") (pin "67") (pinfunction "PE14/FMC_D11/FMC_DA11/LTDC_CLK/SAI2_MCLK_B/SPI4_MOSI/TIM1_CH4_67") (pintype "bidirectional"))
    )
    (net (code "73") (name "/SPI4_NSS") (class "Default")
      (node (ref "J1") (pin "49") (pinfunction "49_49") (pintype "passive"))
      (node (ref "U1") (pin "3") (pinfunction "PE4/DCMI_D4/DFSDM1_DATIN3/FMC_A20/LTDC_B0/SAI1_FS_A/SPI4_NSS/SYS_TRACED1_3") (pintype "bidirectional"))
    )
    (net (code "74") (name "/SPI4_SCK") (class "Default")
      (node (ref "J1") (pin "23") (pinfunction "23_23") (pintype "passive"))
      (node (ref "U1") (pin "1") (pinfunction "PE2/ETH_TXD3/FMC_A23/QUADSPI_BK1_IO2/SAI1_MCLK_A/SPI4_SCK/SYS_TRACECLK_1") (pintype "bidirectional"))
    )
    (net (code "75") (name "/SPI6_MISO") (class "Default")
      (node (ref "J1") (pin "13") (pinfunction "13_13") (pintype "passive"))
      (node (ref "U1") (pin "127") (pinfunction "PG12/FMC_NE4/LPTIM1_IN1/LTDC_B1/LTDC_B4/SDMMC2_D3/SPDIFRX_IN1/SPI6_MISO/USART6_DE/USART6_RTS_127") (pintype "bidirectional"))
    )
    (net (code "76") (name "/SPI6_MOSI") (class "Default")
      (node (ref "J1") (pin "38") (pinfunction "38_38") (pintype "passive"))
      (node (ref "U1") (pin "129") (pinfunction "PG14/ETH_TXD1/FMC_A25/LPTIM1_ETR/LTDC_B0/QUADSPI_BK2_IO3/SPI6_MOSI/SYS_TRACED1/USART6_TX_129") (pintype "bidirectional"))
    )
    (net (code "77") (name "/SPI6_NSS") (class "Default")
      (node (ref "J3") (pin "6") (pinfunction "6_6") (pintype "passive"))
      (node (ref "U1") (pin "93") (pinfunction "PG8/ETH_PPS_OUT/FMC_SDCLK/LTDC_G7/SPDIFRX_IN2/SPI6_NSS/USART6_DE/USART6_RTS_93") (pintype "bidirectional"))
    )
    (net (code "78") (name "/SPI6_SCK") (class "Default")
      (node (ref "J1") (pin "14") (pinfunction "14_14") (pintype "passive"))
      (node (ref "U1") (pin "128") (pinfunction "PG13/ETH_TXD0/FMC_A24/LPTIM1_OUT/LTDC_R0/SPI6_SCK/SYS_TRACED0/USART6_CTS_128") (pintype "bidirectional"))
    )
    (net (code "79") (name "/SYS_JTCK-SWCLK") (class "Default")
      (node (ref "J1") (pin "3") (pinfunction "3_3") (pintype "passive"))
      (node (ref "U1") (pin "109") (pinfunction "PA14/SYS_JTCK-SWCLK_109") (pintype "bidirectional"))
    )
    (net (code "80") (name "/SYS_JTDO-SWO") (class "Default")
      (node (ref "J1") (pin "40") (pinfunction "40_40") (pintype "passive"))
      (node (ref "U1") (pin "133") (pinfunction "PB3/CAN3_RX/I2S1_CK/I2S3_CK/SDMMC2_D2/SPI1_SCK/SPI3_SCK/SPI6_SCK/SYS_JTDO-SWO/TIM2_CH2/UART7_RX_133") (pintype "bidirectional"))
    )
    (net (code "81") (name "/SYS_JTMS-SWDIO") (class "Default")
      (node (ref "J3") (pin "1") (pinfunction "1_1") (pintype "passive"))
      (node (ref "U1") (pin "105") (pinfunction "PA13/SYS_JTMS-SWDIO_105") (pintype "bidirectional"))
    )
    (net (code "82") (name "/TIM1_CH1") (class "Default")
      (node (ref "J2") (pin "9") (pinfunction "9_9") (pintype "passive"))
      (node (ref "U1") (pin "60") (pinfunction "PE9/DAC_EXTI9/DFSDM1_CKOUT/FMC_D6/FMC_DA6/QUADSPI_BK2_IO2/TIM1_CH1/UART7_DE/UART7_RTS_60") (pintype "bidirectional"))
    )
    (net (code "83") (name "/TIM1_CH1N") (class "Default")
      (node (ref "J2") (pin "28") (pinfunction "28_28") (pintype "passive"))
      (node (ref "U1") (pin "74") (pinfunction "PB13/CAN2_TX/DFSDM1_CKIN1/ETH_TXD1/I2S2_CK/SPI2_SCK/TIM1_CH1N/UART5_TX/USART3_CTS/USB_OTG_HS_ULPI_D6/USB_OTG_HS_VBUS_74") (pintype "bidirectional"))
    )
    (net (code "84") (name "/TIM1_CH2") (class "Default")
      (node (ref "J2") (pin "33") (pinfunction "33_33") (pintype "passive"))
      (node (ref "U1") (pin "64") (pinfunction "PE11/ADC1_EXTI11/ADC2_EXTI11/ADC3_EXTI11/DFSDM1_CKIN4/FMC_D8/FMC_DA8/LTDC_G3/SAI2_SD_B/SPI4_NSS/TIM1_CH2_64") (pintype "bidirectional"))
    )
    (net (code "85") (name "/TIM1_CH2N") (class "Default")
      (node (ref "J2") (pin "34") (pinfunction "34_34") (pintype "passive"))
      (node (ref "U1") (pin "63") (pinfunction "PE10/DFSDM1_DATIN4/FMC_D7/FMC_DA7/QUADSPI_BK2_IO3/TIM1_CH2N/UART7_CTS_63") (pintype "bidirectional"))
    )
    (net (code "86") (name "/TIM1_CH3") (class "Default")
      (node (ref "J3") (pin "2") (pinfunction "2_2") (pintype "passive"))
      (node (ref "U1") (pin "102") (pinfunction "PA10/DCMI_D1/LTDC_B1/LTDC_B4/MDIOS_MDIO/TIM1_CH3/USART1_RX/USB_OTG_FS_ID_102") (pintype "bidirectional"))
    )
    (net (code "87") (name "/TIM1_CH3N") (class "Default")
      (node (ref "J2") (pin "32") (pinfunction "32_32") (pintype "passive"))
      (node (ref "U1") (pin "65") (pinfunction "PE12/DFSDM1_DATIN5/FMC_D9/FMC_DA9/LTDC_B4/SAI2_SCK_B/SPI4_SCK/TIM1_CH3N_65") (pintype "bidirectional"))
    )
    (net (code "88") (name "/TIM1_CH4") (class "Default")
      (node (ref "J3") (pin "15") (pinfunction "15_15") (pintype "passive"))
      (node (ref "U1") (pin "103") (pinfunction "PA11/ADC1_EXTI11/ADC2_EXTI11/ADC3_EXTI11/CAN1_RX/I2S2_WS/LTDC_R4/SPI2_NSS/TIM1_CH4/UART4_RX/USART1_CTS/USB_OTG_FS_DM_103") (pintype "bidirectional"))
    )
    (net (code "89") (name "/TIM2_CH1") (class "Default")
      (node (ref "J2") (pin "46") (pinfunction "46_46") (pintype "passive"))
      (node (ref "U1") (pin "34") (pinfunction "PA0/WKUP/ADC1_IN0/ADC2_IN0/ADC3_IN0/ETH_CRS/SAI2_SD_B/SYS_WKUP1/TIM2_CH1/TIM2_ETR/TIM5_CH1/TIM8_ETR/UART4_TX/USART2_CTS_34") (pintype "bidirectional"))
    )
    (net (code "90") (name "/TIM2_CH2") (class "Default")
      (node (ref "J2") (pin "20") (pinfunction "20_20") (pintype "passive"))
      (node (ref "U1") (pin "35") (pinfunction "PA1/ADC1_IN1/ADC2_IN1/ADC3_IN1/ETH_REF_CLK/ETH_RX_CLK/LTDC_R2/QUADSPI_BK1_IO3/SAI2_MCLK_B/TIM2_CH2/TIM5_CH2/UART4_RX/USART2_DE/USART2_RTS_35") (pintype "bidirectional"))
    )
    (net (code "91") (name "/TIM2_CH3") (class "Default")
      (node (ref "J2") (pin "29") (pinfunction "29_29") (pintype "passive"))
      (node (ref "U1") (pin "69") (pinfunction "PB10/DFSDM1_DATIN7/ETH_RX_ER/I2C2_SCL/I2S2_CK/LTDC_G4/QUADSPI_BK1_NCS/SPI2_SCK/TIM2_CH3/USART3_TX/USB_OTG_HS_ULPI_D3_69") (pintype "bidirectional"))
    )
    (net (code "92") (name "/TIM2_CH4") (class "Default")
      (node (ref "J2") (pin "30") (pinfunction "30_30") (pintype "passive"))
      (node (ref "U1") (pin "70") (pinfunction "PB11/ADC1_EXTI11/ADC2_EXTI11/ADC3_EXTI11/DFSDM1_CKIN7/ETH_TX_EN/I2C2_SDA/LTDC_G5/TIM2_CH4/USART3_RX/USB_OTG_HS_ULPI_D4_70") (pintype "bidirectional"))
    )
    (net (code "93") (name "/TIM4_CH1") (class "Default")
      (node (ref "J3") (pin "23") (pinfunction "23_23") (pintype "passive"))
      (node (ref "U1") (pin "81") (pinfunction "PD12/FMC_A17/FMC_ALE/I2C4_SCL/LPTIM1_IN1/QUADSPI_BK1_IO1/SAI2_FS_A/TIM4_CH1/USART3_DE/USART3_RTS_81") (pintype "bidirectional"))
    )
    (net (code "94") (name "/TIM4_CH2") (class "Default")
      (node (ref "J3") (pin "11") (pinfunction "11_11") (pintype "passive"))
      (node (ref "U1") (pin "82") (pinfunction "PD13/FMC_A18/I2C4_SDA/LPTIM1_OUT/QUADSPI_BK1_IO3/SAI2_SCK_A/TIM4_CH2_82") (pintype "bidirectional"))
    )
    (net (code "95") (name "/TIM4_CH3") (class "Default")
      (node (ref "J3") (pin "10") (pinfunction "10_10") (pintype "passive"))
      (node (ref "U1") (pin "85") (pinfunction "PD14/FMC_D0/FMC_DA0/TIM4_CH3/UART8_CTS_85") (pintype "bidirectional"))
    )
    (net (code "96") (name "/TIM4_CH4") (class "Default")
      (node (ref "J3") (pin "22") (pinfunction "22_22") (pintype "passive"))
      (node (ref "U1") (pin "86") (pinfunction "PD15/FMC_D1/FMC_DA1/TIM4_CH4/UART8_DE/UART8_RTS_86") (pintype "bidirectional"))
    )
    (net (code "97") (name "/TIM5_CH3") (class "Default")
      (node (ref "J2") (pin "19") (pinfunction "19_19") (pintype "passive"))
      (node (ref "U1") (pin "36") (pinfunction "PA2/ADC1_IN2/ADC2_IN2/ADC3_IN2/ETH_MDIO/LTDC_R1/MDIOS_MDIO/SAI2_SCK_B/SYS_WKUP2/TIM2_CH3/TIM5_CH3/TIM9_CH1/USART2_TX_36") (pintype "bidirectional"))
    )
    (net (code "98") (name "/TIM5_CH4") (class "Default")
      (node (ref "J2") (pin "45") (pinfunction "45_45") (pintype "passive"))
      (node (ref "U1") (pin "37") (pinfunction "PA3/ADC1_IN3/ADC2_IN3/ADC3_IN3/ETH_COL/LTDC_B2/LTDC_B5/TIM2_CH4/TIM5_CH4/TIM9_CH2/USART2_RX/USB_OTG_HS_ULPI_D0_37") (pintype "bidirectional"))
    )
    (net (code "99") (name "/TIM8_CH1") (class "Default")
      (node (ref "J3") (pin "5") (pinfunction "5_5") (pintype "passive"))
      (node (ref "U1") (pin "96") (pinfunction "PC6/DCMI_D0/DFSDM1_CKIN3/FMC_NWAIT/I2S2_MCK/LTDC_HSYNC/SDMMC1_D6/SDMMC2_D6/TIM3_CH1/TIM8_CH1/USART6_TX_96") (pintype "bidirectional"))
    )
    (net (code "100") (name "/TIM8_CH1N") (class "Default")
      (node (ref "J2") (pin "16") (pinfunction "16_16") (pintype "passive"))
      (node (ref "U1") (pin "43") (pinfunction "PA7/ADC1_IN7/ADC2_IN7/ETH_CRS_DV/ETH_RX_DV/FMC_SDNWE/I2S1_SD/SPI1_MOSI/SPI6_MOSI/TIM14_CH1/TIM1_CH1N/TIM3_CH2/TIM8_CH1N_43") (pintype "bidirectional"))
    )
    (net (code "101") (name "/TIM8_CH2") (class "Default")
      (node (ref "J3") (pin "18") (pinfunction "18_18") (pintype "passive"))
      (node (ref "U1") (pin "97") (pinfunction "PC7/DCMI_D1/DFSDM1_DATIN3/FMC_NE1/I2S3_MCK/LTDC_G6/SDMMC1_D7/SDMMC2_D7/TIM3_CH2/TIM8_CH2/USART6_RX_97") (pintype "bidirectional"))
    )
    (net (code "102") (name "/TIM8_CH2N") (class "Default")
      (node (ref "J2") (pin "2") (pinfunction "2_2") (pintype "passive"))
      (node (ref "U1") (pin "75") (pinfunction "PB14/DFSDM1_DATIN2/SDMMC2_D0/SPI2_MISO/TIM12_CH1/TIM1_CH2N/TIM8_CH2N/UART4_DE/UART4_RTS/USART1_TX/USART3_DE/USART3_RTS/USB_OTG_HS_DM_75") (pintype "bidirectional"))
    )
    (net (code "103") (name "/TIM8_CH3") (class "Default")
      (node (ref "J3") (pin "4") (pinfunction "4_4") (pintype "passive"))
      (node (ref "U1") (pin "98") (pinfunction "PC8/DCMI_D2/FMC_NCE3/FMC_NE2/SDMMC1_D0/SYS_TRACED1/TIM3_CH3/TIM8_CH3/UART5_DE/UART5_RTS/USART6_CK_98") (pintype "bidirectional"))
    )
    (net (code "104") (name "/TIM8_CH3N") (class "Default")
      (node (ref "J3") (pin "26") (pinfunction "26_26") (pintype "passive"))
      (node (ref "U1") (pin "76") (pinfunction "PB15/DFSDM1_CKIN2/I2S2_SD/RTC_REFIN/SDMMC2_D1/SPI2_MOSI/TIM12_CH2/TIM1_CH3N/TIM8_CH3N/UART4_CTS/USART1_RX/USB_OTG_HS_DP_76") (pintype "bidirectional"))
    )
    (net (code "105") (name "/TIM8_CH4") (class "Default")
      (node (ref "J3") (pin "17") (pinfunction "17_17") (pintype "passive"))
      (node (ref "U1") (pin "99") (pinfunction "PC9/DAC_EXTI9/DCMI_D3/I2C3_SDA/I2S_CKIN/LTDC_B2/LTDC_G3/QUADSPI_BK1_IO0/RCC_MCO_2/SDMMC1_D1/TIM3_CH4/TIM8_CH4/UART5_CTS_99") (pintype "bidirectional"))
    )
    (net (code "106") (name "/TIM9_CH1") (class "Default")
      (node (ref "J1") (pin "25") (pinfunction "25_25") (pintype "passive"))
      (node (ref "U1") (pin "4") (pinfunction "PE5/DCMI_D6/DFSDM1_CKIN3/FMC_A21/LTDC_G0/SAI1_SCK_A/SPI4_MISO/SYS_TRACED2/TIM9_CH1_4") (pintype "bidirectional"))
    )
    (net (code "107") (name "/TIM9_CH2") (class "Default")
      (node (ref "J1") (pin "50") (pinfunction "50_50") (pintype "passive"))
      (node (ref "U1") (pin "5") (pinfunction "PE6/DCMI_D7/FMC_A22/LTDC_G1/SAI1_SD_A/SAI2_MCLK_B/SPI4_MOSI/SYS_TRACED3/TIM1_BKIN2/TIM9_CH2_5") (pintype "bidirectional"))
    )
    (net (code "108") (name "/UART4_DE") (class "Default")
      (node (ref "J1") (pin "4") (pinfunction "4_4") (pintype "passive"))
      (node (ref "U1") (pin "110") (pinfunction "PA15/CAN3_TX/CEC/I2S1_WS/I2S3_WS/SPI1_NSS/SPI3_NSS/SPI6_NSS/SYS_JTDI/TIM2_CH1/TIM2_ETR/UART4_DE/UART4_RTS/UART7_TX_110") (pintype "bidirectional"))
    )
    (net (code "109") (name "/UART4_RX") (class "Default")
      (node (ref "J1") (pin "6") (pinfunction "6_6") (pintype "passive"))
      (node (ref "U1") (pin "112") (pinfunction "PC11/ADC1_EXTI11/ADC2_EXTI11/ADC3_EXTI11/DCMI_D4/DFSDM1_DATIN5/QUADSPI_BK2_NCS/SDMMC1_D3/SPI3_MISO/UART4_RX/USART3_RX_112") (pintype "bidirectional"))
    )
    (net (code "110") (name "/UART4_TX") (class "Default")
      (node (ref "J1") (pin "5") (pinfunction "5_5") (pintype "passive"))
      (node (ref "U1") (pin "111") (pinfunction "PC10/DCMI_D8/DFSDM1_CKIN5/I2S3_CK/LTDC_R2/QUADSPI_BK1_IO1/SDMMC1_D2/SPI3_SCK/UART4_TX/USART3_TX_111") (pintype "bidirectional"))
    )
    (net (code "111") (name "/UART5_RX") (class "Default")
      (node (ref "J1") (pin "8") (pinfunction "8_8") (pintype "passive"))
      (node (ref "U1") (pin "116") (pinfunction "PD2/DCMI_D11/SDMMC1_CMD/SYS_TRACED2/TIM3_ETR/UART5_RX_116") (pintype "bidirectional"))
    )
    (net (code "112") (name "/UART5_TX") (class "Default")
      (node (ref "J1") (pin "7") (pinfunction "7_7") (pintype "passive"))
      (node (ref "U1") (pin "113") (pinfunction "PC12/DCMI_D9/I2S3_SD/SDMMC1_CK/SPI3_MOSI/SYS_TRACED3/UART5_TX/USART3_CK_113") (pintype "bidirectional"))
    )
    (net (code "113") (name "/USART1_DE") (class "Default")
      (node (ref "J3") (pin "14") (pinfunction "14_14") (pintype "passive"))
      (node (ref "U1") (pin "104") (pinfunction "PA12/CAN1_TX/I2S2_CK/LTDC_R5/SAI2_FS_B/SPI2_SCK/TIM1_ETR/UART4_TX/USART1_DE/USART1_RTS/USB_OTG_FS_DP_104") (pintype "bidirectional"))
    )
    (net (code "114") (name "/USART1_RX") (class "Default")
      (node (ref "J1") (pin "30") (pinfunction "30_30") (pintype "passive"))
      (node (ref "U1") (pin "137") (pinfunction "PB7/DCMI_VSYNC/DFSDM1_CKIN5/FMC_NL/I2C1_SDA/I2C4_SDA/TIM4_CH2/USART1_RX_137") (pintype "bidirectional"))
    )
    (net (code "115") (name "/USART1_TX") (class "Default")
      (node (ref "J3") (pin "16") (pinfunction "16_16") (pintype "passive"))
      (node (ref "U1") (pin "101") (pinfunction "PA9/DAC_EXTI9/DCMI_D0/I2C3_SMBA/I2S2_CK/LTDC_R5/SPI2_SCK/TIM1_CH2/USART1_TX/USB_OTG_FS_VBUS_101") (pintype "bidirectional"))
    )
    (net (code "116") (name "/USART3_RX") (class "Default")
      (node (ref "J3") (pin "13") (pinfunction "13_13") (pintype "passive"))
      (node (ref "U1") (pin "78") (pinfunction "PD9/DAC_EXTI9/DFSDM1_DATIN3/FMC_D14/FMC_DA14/USART3_RX_78") (pintype "bidirectional"))
    )
    (net (code "117") (name "/USART3_TX") (class "Default")
      (node (ref "J3") (pin "25") (pinfunction "25_25") (pintype "passive"))
      (node (ref "U1") (pin "77") (pinfunction "PD8/DFSDM1_CKIN3/FMC_D13/FMC_DA13/SPDIFRX_IN1/USART3_TX_77") (pintype "bidirectional"))
    )
    (net (code "118") (name "GND") (class "Default")
      (node (ref "C1") (pin "2") (pinfunction "2_2") (pintype "passive"))
      (node (ref "C10") (pin "1") (pinfunction "1_1") (pintype "passive"))
      (node (ref "C11") (pin "2") (pinfunction "2_2") (pintype "passive"))
      (node (ref "C12") (pin "2") (pinfunction "2_2") (pintype "passive"))
      (node (ref "C13") (pin "1") (pinfunction "1_1") (pintype "passive"))
      (node (ref "C14") (pin "1") (pinfunction "1_1") (pintype "passive"))
      (node (ref "C15") (pin "1") (pinfunction "1_1") (pintype "passive"))
      (node (ref "C16") (pin "1") (pinfunction "1_1") (pintype "passive"))
      (node (ref "C17") (pin "1") (pinfunction "1_1") (pintype "passive"))
      (node (ref "C18") (pin "1") (pinfunction "1_1") (pintype "passive"))
      (node (ref "C19") (pin "1") (pinfunction "1_1") (pintype "passive"))
      (node (ref "C2") (pin "1") (pinfunction "1_1") (pintype "passive"))
      (node (ref "C20") (pin "1") (pinfunction "1_1") (pintype "passive"))
      (node (ref "C21") (pin "1") (pinfunction "1_1") (pintype "passive"))
      (node (ref "C3") (pin "1") (pinfunction "1_1") (pintype "passive"))
      (node (ref "C4") (pin "1") (pinfunction "1_1") (pintype "passive"))
      (node (ref "C5") (pin "1") (pinfunction "1_1") (pintype "passive"))
      (node (ref "C6") (pin "1") (pinfunction "1_1") (pintype "passive"))
      (node (ref "C7") (pin "1") (pinfunction "1_1") (pintype "passive"))
      (node (ref "C8") (pin "1") (pinfunction "1_1") (pintype "passive"))
      (node (ref "C9") (pin "1") (pinfunction "1_1") (pintype "passive"))
      (node (ref "D1") (pin "1") (pinfunction "C_1") (pintype "passive"))
      (node (ref "J1") (pin "1") (pinfunction "1_1") (pintype "passive"))
      (node (ref "J1") (pin "26") (pinfunction "26_26") (pintype "passive"))
      (node (ref "J2") (pin "1") (pinfunction "1_1") (pintype "passive"))
      (node (ref "J2") (pin "26") (pinfunction "26_26") (pintype "passive"))
      (node (ref "J2") (pin "39") (pinfunction "39_39") (pintype "passive"))
      (node (ref "R1") (pin "1") (pinfunction "1_1") (pintype "passive"))
      (node (ref "S1") (pin "1") (pinfunction "1_1") (pintype "passive"))
      (node (ref "S1") (pin "3") (pinfunction "3_3") (pintype "passive"))
      (node (ref "U1") (pin "107") (pinfunction "VSS_107") (pintype "power_in"))
      (node (ref "U1") (pin "120") (pinfunction "VSS_120") (pintype "power_in"))
      (node (ref "U1") (pin "130") (pinfunction "VSS_130") (pintype "power_in"))
      (node (ref "U1") (pin "16") (pinfunction "VSS_16") (pintype "power_in"))
      (node (ref "U1") (pin "31") (pinfunction "VSSA_31") (pintype "power_in"))
      (node (ref "U1") (pin "38") (pinfunction "VSS_38") (pintype "power_in"))
      (node (ref "U1") (pin "51") (pinfunction "VSS_51") (pintype "power_in"))
      (node (ref "U1") (pin "61") (pinfunction "VSS_61") (pintype "power_in"))
      (node (ref "U1") (pin "83") (pinfunction "VSS_83") (pintype "power_in"))
      (node (ref "U1") (pin "94") (pinfunction "VSS_94") (pintype "power_in"))
      (node (ref "Y1") (pin "2") (pinfunction "GND_2") (pintype "power_in"))
      (node (ref "Y1") (pin "4") (pinfunction "GND_4") (pintype "power_in"))
    )
    (net (code "119") (name "Net-(C20-Pad2)") (class "Default")
      (node (ref "C20") (pin "2") (pinfunction "2_2") (pintype "passive"))
      (node (ref "R3") (pin "1") (pinfunction "1_1") (pintype "passive"))
      (node (ref "Y1") (pin "1") (pinfunction "1_1") (pintype "passive"))
    )
    (net (code "120") (name "Net-(D1-A)") (class "Default")
      (node (ref "D1") (pin "2") (pinfunction "A_2") (pintype "passive"))
      (node (ref "R4") (pin "1") (pinfunction "1_1") (pintype "passive"))
    )
    (net (code "121") (name "Net-(U1-VCAP_1)") (class "Default")
      (node (ref "C11") (pin "1") (pinfunction "1_1") (pintype "passive"))
      (node (ref "U1") (pin "71") (pinfunction "VCAP_1_71") (pintype "power_in"))
    )
    (net (code "122") (name "Net-(U1-VCAP_2)") (class "Default")
      (node (ref "C12") (pin "1") (pinfunction "1_1") (pintype "passive"))
      (node (ref "U1") (pin "106") (pinfunction "VCAP_2_106") (pintype "power_in"))
    )
    (net (code "123") (name "VDD") (class "Default")
      (node (ref "C1") (pin "1") (pinfunction "1_1") (pintype "passive"))
      (node (ref "C10") (pin "2") (pinfunction "2_2") (pintype "passive"))
      (node (ref "C13") (pin "2") (pinfunction "2_2") (pintype "passive"))
      (node (ref "C14") (pin "2") (pinfunction "2_2") (pintype "passive"))
      (node (ref "C15") (pin "2") (pinfunction "2_2") (pintype "passive"))
      (node (ref "C18") (pin "2") (pinfunction "2_2") (pintype "passive"))
      (node (ref "C2") (pin "2") (pinfunction "2_2") (pintype "passive"))
      (node (ref "C3") (pin "2") (pinfunction "2_2") (pintype "passive"))
      (node (ref "C4") (pin "2") (pinfunction "2_2") (pintype "passive"))
      (node (ref "C5") (pin "2") (pinfunction "2_2") (pintype "passive"))
      (node (ref "C6") (pin "2") (pinfunction "2_2") (pintype "passive"))
      (node (ref "C7") (pin "2") (pinfunction "2_2") (pintype "passive"))
      (node (ref "C8") (pin "2") (pinfunction "2_2") (pintype "passive"))
      (node (ref "C9") (pin "2") (pinfunction "2_2") (pintype "passive"))
      (node (ref "FB1") (pin "1") (pinfunction "1_1") (pintype "passive"))
      (node (ref "J1") (pin "2") (pinfunction "2_2") (pintype "passive"))
      (node (ref "J2") (pin "27") (pinfunction "27_27") (pintype "passive"))
      (node (ref "R2") (pin "2") (pinfunction "2_2") (pintype "passive"))
      (node (ref "R5") (pin "1") (pinfunction "1_1") (pintype "passive"))
      (node (ref "U1") (pin "108") (pinfunction "VDD_108") (pintype "power_in"))
      (node (ref "U1") (pin "121") (pinfunction "VDDSDMMC_121") (pintype "power_in"))
      (node (ref "U1") (pin "131") (pinfunction "VDD_131") (pintype "power_in"))
      (node (ref "U1") (pin "144") (pinfunction "VDD_144") (pintype "power_in"))
      (node (ref "U1") (pin "17") (pinfunction "VDD_17") (pintype "power_in"))
      (node (ref "U1") (pin "30") (pinfunction "VDD_30") (pintype "power_in"))
      (node (ref "U1") (pin "39") (pinfunction "VDD_39") (pintype "power_in"))
      (node (ref "U1") (pin "52") (pinfunction "VDD_52") (pintype "power_in"))
      (node (ref "U1") (pin "6") (pinfunction "VBAT_6") (pintype "power_in"))
      (node (ref "U1") (pin "62") (pinfunction "VDD_62") (pintype "power_in"))
      (node (ref "U1") (pin "72") (pinfunction "VDD_72") (pintype "power_in"))
      (node (ref "U1") (pin "84") (pinfunction "VDD_84") (pintype "power_in"))
      (node (ref "U1") (pin "95") (pinfunction "VDDUSB_95") (pintype "power_in"))
    )
    (net (code "124") (name "VDDA") (class "Default")
      (node (ref "C17") (pin "2") (pinfunction "2_2") (pintype "passive"))
      (node (ref "C19") (pin "2") (pinfunction "2_2") (pintype "passive"))
      (node (ref "FB1") (pin "2") (pinfunction "2_2") (pintype "passive"))
      (node (ref "U1") (pin "32") (pinfunction "VREF+_32") (pintype "passive"))
      (node (ref "U1") (pin "33") (pinfunction "VDDA_33") (pintype "power_in"))
    )
    (net (code "125") (name "unconnected-(J1-Pad22)") (class "Default")
      (node (ref "J1") (pin "22") (pinfunction "22_22") (pintype "passive"))
    )
    (net (code "126") (name "unconnected-(J1-Pad27)") (class "Default")
      (node (ref "J1") (pin "27") (pinfunction "27_27") (pintype "passive"))
    )
    (net (code "127") (name "unconnected-(J1-Pad28)") (class "Default")
      (node (ref "J1") (pin "28") (pinfunction "28_28") (pintype "passive"))
    )
    (net (code "128") (name "unconnected-(J1-Pad29)") (class "Default")
      (node (ref "J1") (pin "29") (pinfunction "29_29") (pintype "passive"))
    )
    (net (code "129") (name "unconnected-(J1-Pad48)") (class "Default")
      (node (ref "J1") (pin "48") (pinfunction "48_48") (pintype "passive"))
    )
    (net (code "130") (name "unconnected-(J2-Pad4)") (class "Default")
      (node (ref "J2") (pin "4") (pinfunction "4_4") (pintype "passive"))
    )
    (net (code "131") (name "unconnected-(J2-Pad5)") (class "Default")
      (node (ref "J2") (pin "5") (pinfunction "5_5") (pintype "passive"))
    )
    (net (code "132") (name "unconnected-(S1-PAD-Pad5)") (class "Default")
      (node (ref "S1") (pin "5") (pinfunction "PAD_5") (pintype "passive"))
    )
  )
)
